# 2_mb_conn.net
KiCad netlist of a schematic drawn in Altium Designer
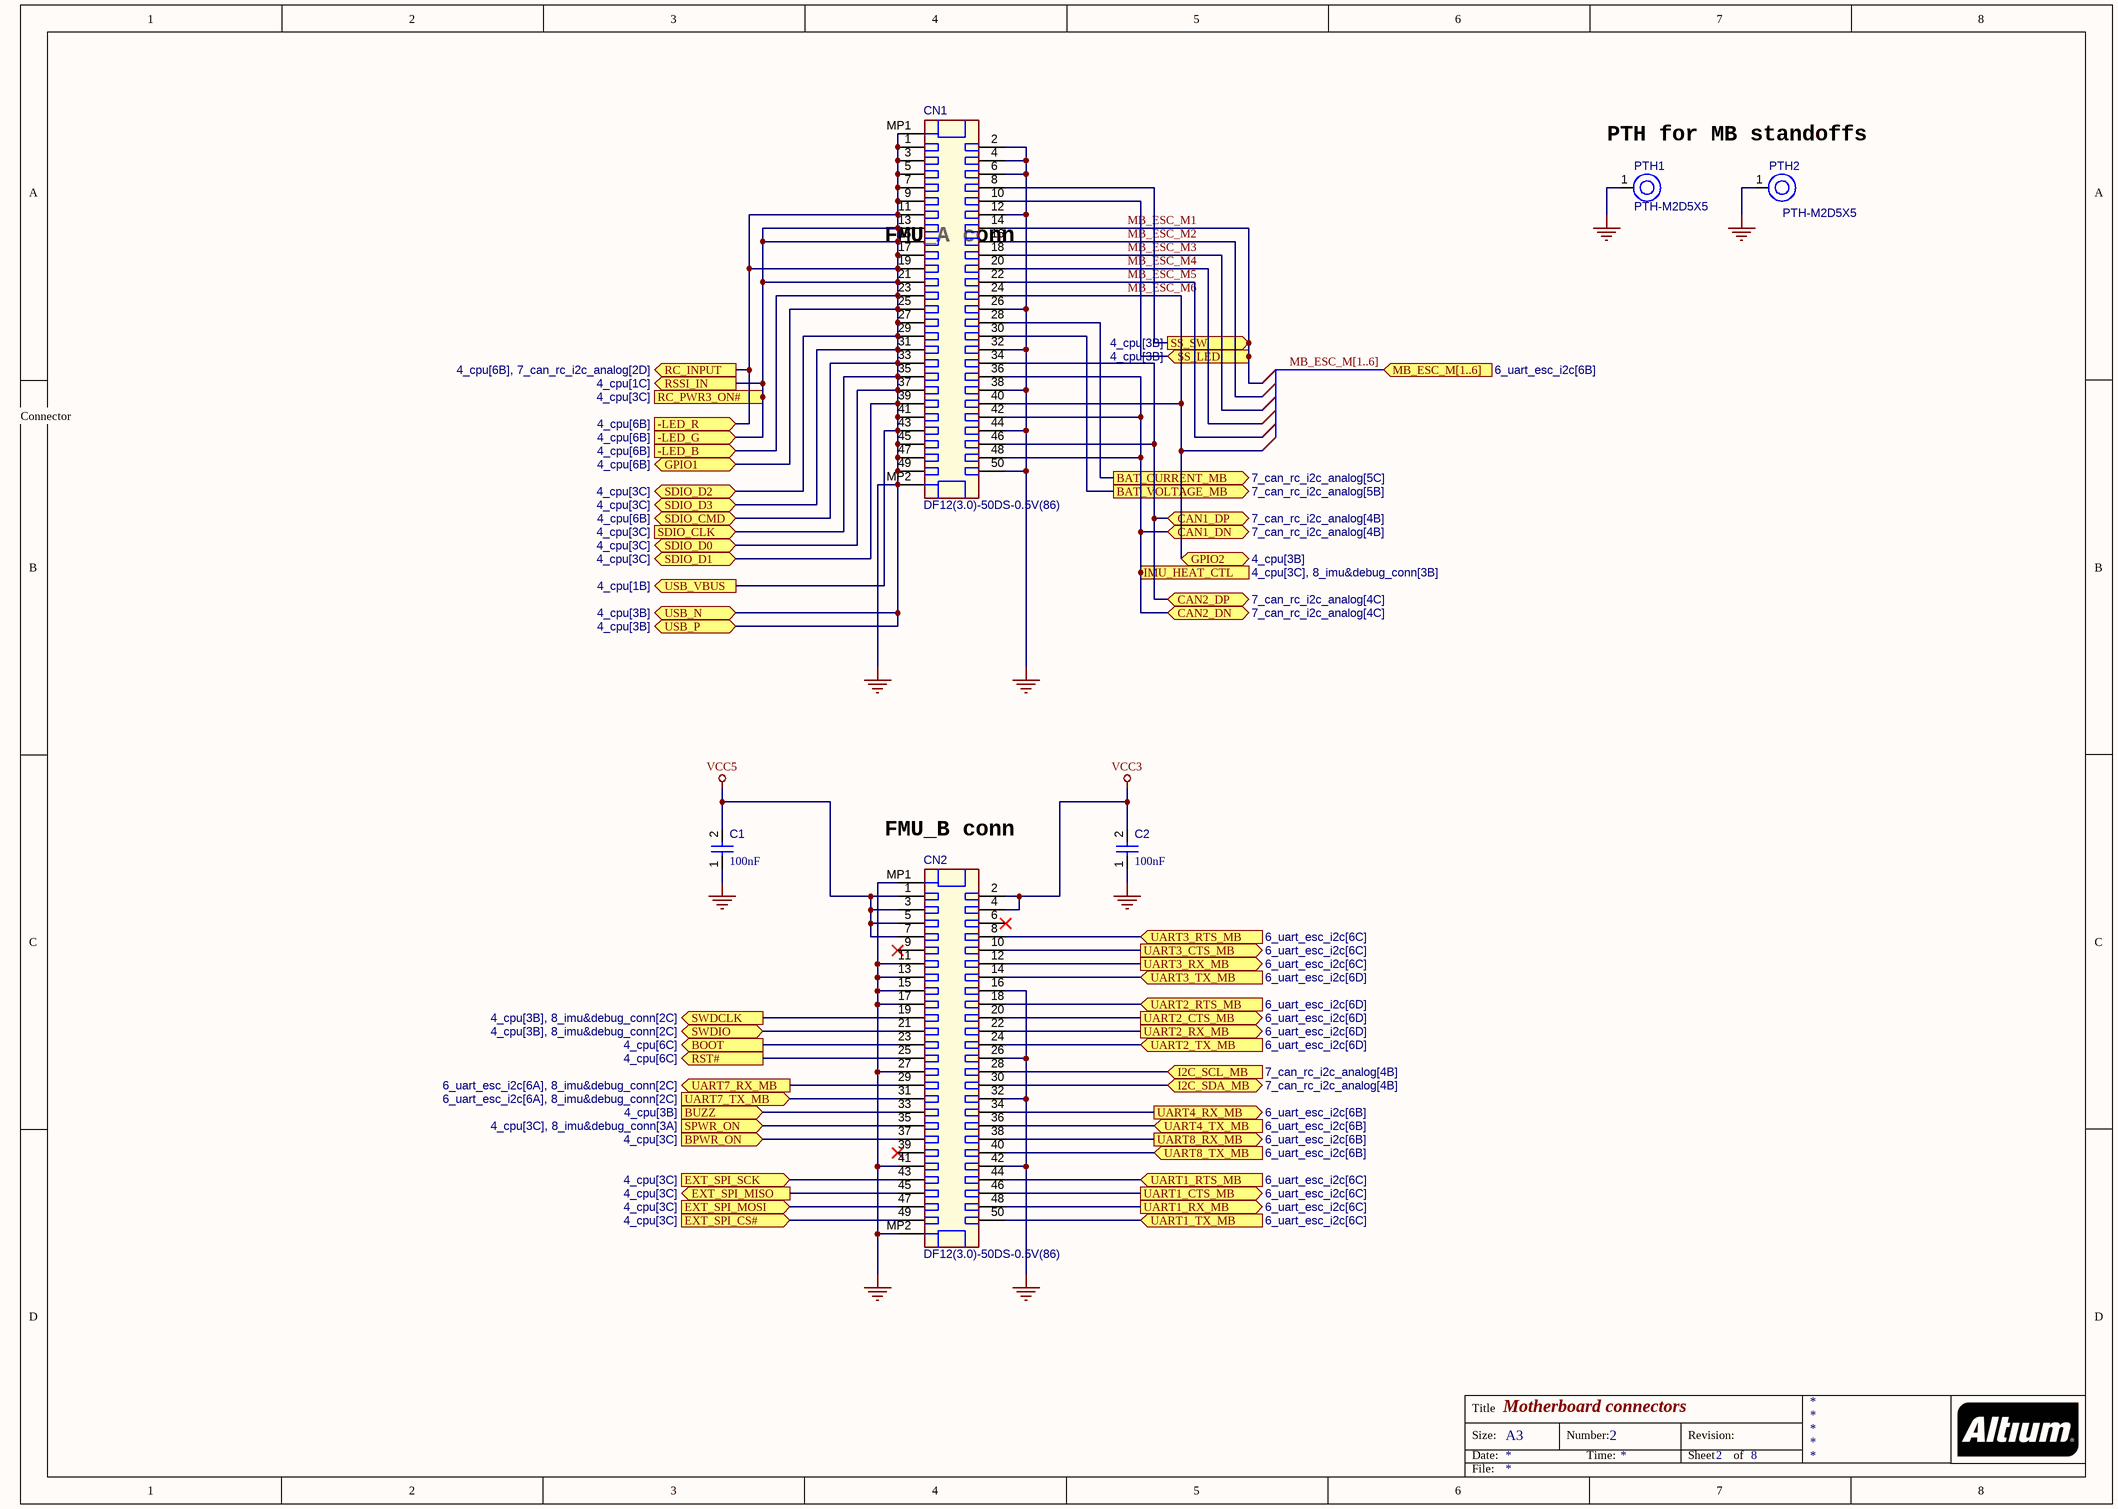
[diagram p0: 2_mb_conn.SchDoc]

(export (version "E")
  (design (tool "Eeschema 10.0.6"))
  (components
    (comp (ref "C1")
      (value "100nF")
      (footprint "CAPC0402(1005)60_L")
      (description "Chip Capacitor, 100nF +/-20%, 10V, 0402, Thickness 0.6 mm")
      (fields (field (name "TOLERANCE") "20%") (field (name "Comment") "Capacitor 100nF +/-20% 10V 0402"))
      (libsource (lib "SKA- Automa玢o de Engenharias") (part "CAP-NP-2"))
    )
    (comp (ref "C2")
      (value "100nF")
      (footprint "CAPC0402(1005)60_L")
      (description "Chip Capacitor, 100nF +/-20%, 10V, 0402, Thickness 0.6 mm")
      (fields (field (name "TOLERANCE") "20%") (field (name "Comment") "Capacitor 100nF +/-20% 10V 0402"))
      (libsource (lib "SKA- Automa玢o de Engenharias") (part "CAP-NP-2"))
    )
    (comp (ref "CN1")
      (value "DF12(3.0)-50DS-0.5V(86)")
      (footprint "HIRO-DF12(3.0)-50DS-0.5V_V")
      (description "Receptacle Connector, 50 V, 0.3 A, -45 to 125 degC, RoHS, Tape and Reel")
      (fields (field (name "PART NUMBER") "DF12"))
      (libsource (lib "SKA- Automa玢o de Engenharias") (part "CMP-00111-4"))
    )
    (comp (ref "CN2")
      (value "DF12(3.0)-50DS-0.5V(86)")
      (footprint "HIRO-DF12(3.0)-50DS-0.5V_V")
      (description "Receptacle Connector, 50 V, 0.3 A, -45 to 125 degC, RoHS, Tape and Reel")
      (fields (field (name "PART NUMBER") "DF12"))
      (libsource (lib "SKA- Automa玢o de Engenharias") (part "CMP-00111-4"))
    )
    (comp (ref "PTH1")
      (value "PTH-M2D5X5")
      (footprint "PTH-M2D5X5")
      (description "M2 PTH (2.5mm), 5mm pad")
      (libsource (lib "<Company> Server") (part "CMP-00028-00000-1"))
    )
    (comp (ref "PTH2")
      (value "PTH-M2D5X5")
      (footprint "PTH-M2D5X5")
      (description "M2 PTH (2.5mm), 5mm pad")
      (libsource (lib "<Company> Server") (part "CMP-00028-00000-1"))
    )
  )
  (nets
    (net (code "1") (name "/BAT_CURRENT_MB") (class "Default")
      (node (ref "CN1") (pin "28") (pinfunction "28_28") (pintype "passive"))
    )
    (net (code "2") (name "/BAT_VOLTAGE_MB") (class "Default")
      (node (ref "CN1") (pin "30") (pinfunction "30_30") (pintype "passive"))
    )
    (net (code "3") (name "/BOOT") (class "Default")
      (node (ref "CN2") (pin "23") (pinfunction "23_23") (pintype "passive"))
    )
    (net (code "4") (name "/BPWR_ON") (class "Default")
      (node (ref "CN2") (pin "37") (pinfunction "37_37") (pintype "passive"))
    )
    (net (code "5") (name "/BUZZ") (class "Default")
      (node (ref "CN2") (pin "33") (pinfunction "33_33") (pintype "passive"))
    )
    (net (code "6") (name "/CAN1_DN") (class "Default")
      (node (ref "CN1") (pin "36") (pinfunction "36_36") (pintype "passive"))
      (node (ref "CN1") (pin "42") (pinfunction "42_42") (pintype "passive"))
      (node (ref "CN1") (pin "48") (pinfunction "48_48") (pintype "passive"))
    )
    (net (code "7") (name "/CAN1_DP") (class "Default")
      (node (ref "CN1") (pin "34") (pinfunction "34_34") (pintype "passive"))
      (node (ref "CN1") (pin "46") (pinfunction "46_46") (pintype "passive"))
    )
    (net (code "8") (name "/EXT_SPI_CS#") (class "Default")
      (node (ref "CN2") (pin "49") (pinfunction "49_49") (pintype "passive"))
    )
    (net (code "9") (name "/EXT_SPI_MISO") (class "Default")
      (node (ref "CN2") (pin "45") (pinfunction "45_45") (pintype "passive"))
    )
    (net (code "10") (name "/EXT_SPI_MOSI") (class "Default")
      (node (ref "CN2") (pin "47") (pinfunction "47_47") (pintype "passive"))
    )
    (net (code "11") (name "/EXT_SPI_SCK") (class "Default")
      (node (ref "CN2") (pin "43") (pinfunction "43_43") (pintype "passive"))
    )
    (net (code "12") (name "/I2C_SCL_MB") (class "Default")
      (node (ref "CN2") (pin "28") (pinfunction "28_28") (pintype "passive"))
    )
    (net (code "13") (name "/I2C_SDA_MB") (class "Default")
      (node (ref "CN2") (pin "30") (pinfunction "30_30") (pintype "passive"))
    )
    (net (code "14") (name "/MB_ESC_M1") (class "Default")
      (node (ref "CN1") (pin "10") (pinfunction "10_10") (pintype "passive"))
      (node (ref "CN1") (pin "14") (pinfunction "14_14") (pintype "passive"))
      (node (ref "CN1") (pin "8") (pinfunction "8_8") (pintype "passive"))
    )
    (net (code "15") (name "/MB_ESC_M2") (class "Default")
      (node (ref "CN1") (pin "16") (pinfunction "16_16") (pintype "passive"))
    )
    (net (code "16") (name "/MB_ESC_M3") (class "Default")
      (node (ref "CN1") (pin "18") (pinfunction "18_18") (pintype "passive"))
    )
    (net (code "17") (name "/MB_ESC_M4") (class "Default")
      (node (ref "CN1") (pin "20") (pinfunction "20_20") (pintype "passive"))
    )
    (net (code "18") (name "/MB_ESC_M5") (class "Default")
      (node (ref "CN1") (pin "22") (pinfunction "22_22") (pintype "passive"))
    )
    (net (code "19") (name "/MB_ESC_M6") (class "Default")
      (node (ref "CN1") (pin "24") (pinfunction "24_24") (pintype "passive"))
      (node (ref "CN1") (pin "40") (pinfunction "40_40") (pintype "passive"))
    )
    (net (code "21") (name "/RST#") (class "Default")
      (node (ref "CN2") (pin "25") (pinfunction "25_25") (pintype "passive"))
    )
    (net (code "22") (name "/SPWR_ON") (class "Default")
      (node (ref "CN2") (pin "35") (pinfunction "35_35") (pintype "passive"))
    )
    (net (code "23") (name "/SWDCLK") (class "Default")
      (node (ref "CN2") (pin "19") (pinfunction "19_19") (pintype "passive"))
    )
    (net (code "24") (name "/SWDIO") (class "Default")
      (node (ref "CN2") (pin "21") (pinfunction "21_21") (pintype "passive"))
    )
    (net (code "25") (name "/UART1_CTS_MB") (class "Default")
      (node (ref "CN2") (pin "46") (pinfunction "46_46") (pintype "passive"))
    )
    (net (code "26") (name "/UART1_RTS_MB") (class "Default")
      (node (ref "CN2") (pin "44") (pinfunction "44_44") (pintype "passive"))
    )
    (net (code "27") (name "/UART1_RX_MB") (class "Default")
      (node (ref "CN2") (pin "48") (pinfunction "48_48") (pintype "passive"))
    )
    (net (code "28") (name "/UART1_TX_MB") (class "Default")
      (node (ref "CN2") (pin "50") (pinfunction "50_50") (pintype "passive"))
    )
    (net (code "29") (name "/UART2_CTS_MB") (class "Default")
      (node (ref "CN2") (pin "20") (pinfunction "20_20") (pintype "passive"))
    )
    (net (code "30") (name "/UART2_RTS_MB") (class "Default")
      (node (ref "CN2") (pin "18") (pinfunction "18_18") (pintype "passive"))
    )
    (net (code "31") (name "/UART2_RX_MB") (class "Default")
      (node (ref "CN2") (pin "22") (pinfunction "22_22") (pintype "passive"))
    )
    (net (code "32") (name "/UART2_TX_MB") (class "Default")
      (node (ref "CN2") (pin "24") (pinfunction "24_24") (pintype "passive"))
    )
    (net (code "33") (name "/UART3_CTS_MB") (class "Default")
      (node (ref "CN2") (pin "10") (pinfunction "10_10") (pintype "passive"))
    )
    (net (code "34") (name "/UART3_RTS_MB") (class "Default")
      (node (ref "CN2") (pin "8") (pinfunction "8_8") (pintype "passive"))
    )
    (net (code "35") (name "/UART3_RX_MB") (class "Default")
      (node (ref "CN2") (pin "12") (pinfunction "12_12") (pintype "passive"))
    )
    (net (code "36") (name "/UART3_TX_MB") (class "Default")
      (node (ref "CN2") (pin "14") (pinfunction "14_14") (pintype "passive"))
    )
    (net (code "37") (name "/UART4_RX_MB") (class "Default")
      (node (ref "CN2") (pin "34") (pinfunction "34_34") (pintype "passive"))
    )
    (net (code "38") (name "/UART4_TX_MB") (class "Default")
      (node (ref "CN2") (pin "36") (pinfunction "36_36") (pintype "passive"))
    )
    (net (code "39") (name "/UART7_RX_MB") (class "Default")
      (node (ref "CN2") (pin "29") (pinfunction "29_29") (pintype "passive"))
    )
    (net (code "40") (name "/UART7_TX_MB") (class "Default")
      (node (ref "CN2") (pin "31") (pinfunction "31_31") (pintype "passive"))
    )
    (net (code "41") (name "/UART8_RX_MB") (class "Default")
      (node (ref "CN2") (pin "38") (pinfunction "38_38") (pintype "passive"))
    )
    (net (code "42") (name "/UART8_TX_MB") (class "Default")
      (node (ref "CN2") (pin "40") (pinfunction "40_40") (pintype "passive"))
    )
    (net (code "43") (name "GND") (class "Default")
      (node (ref "C1") (pin "1") (pinfunction "1_1") (pintype "passive"))
      (node (ref "C2") (pin "1") (pinfunction "1_1") (pintype "passive"))
      (node (ref "CN1") (pin "1") (pinfunction "1_1") (pintype "passive"))
      (node (ref "CN1") (pin "11") (pinfunction "11_11") (pintype "passive"))
      (node (ref "CN1") (pin "12") (pinfunction "12_12") (pintype "passive"))
      (node (ref "CN1") (pin "13") (pinfunction "13_13") (pintype "passive"))
      (node (ref "CN1") (pin "15") (pinfunction "15_15") (pintype "passive"))
      (node (ref "CN1") (pin "17") (pinfunction "17_17") (pintype "passive"))
      (node (ref "CN1") (pin "19") (pinfunction "19_19") (pintype "passive"))
      (node (ref "CN1") (pin "2") (pinfunction "2_2") (pintype "passive"))
      (node (ref "CN1") (pin "21") (pinfunction "21_21") (pintype "passive"))
      (node (ref "CN1") (pin "23") (pinfunction "23_23") (pintype "passive"))
      (node (ref "CN1") (pin "25") (pinfunction "25_25") (pintype "passive"))
      (node (ref "CN1") (pin "26") (pinfunction "26_26") (pintype "passive"))
      (node (ref "CN1") (pin "27") (pinfunction "27_27") (pintype "passive"))
      (node (ref "CN1") (pin "29") (pinfunction "29_29") (pintype "passive"))
      (node (ref "CN1") (pin "3") (pinfunction "3_3") (pintype "passive"))
      (node (ref "CN1") (pin "31") (pinfunction "31_31") (pintype "passive"))
      (node (ref "CN1") (pin "32") (pinfunction "32_32") (pintype "passive"))
      (node (ref "CN1") (pin "33") (pinfunction "33_33") (pintype "passive"))
      (node (ref "CN1") (pin "35") (pinfunction "35_35") (pintype "passive"))
      (node (ref "CN1") (pin "37") (pinfunction "37_37") (pintype "passive"))
      (node (ref "CN1") (pin "38") (pinfunction "38_38") (pintype "passive"))
      (node (ref "CN1") (pin "39") (pinfunction "39_39") (pintype "passive"))
      (node (ref "CN1") (pin "4") (pinfunction "4_4") (pintype "passive"))
      (node (ref "CN1") (pin "41") (pinfunction "41_41") (pintype "passive"))
      (node (ref "CN1") (pin "43") (pinfunction "43_43") (pintype "passive"))
      (node (ref "CN1") (pin "44") (pinfunction "44_44") (pintype "passive"))
      (node (ref "CN1") (pin "45") (pinfunction "45_45") (pintype "passive"))
      (node (ref "CN1") (pin "47") (pinfunction "47_47") (pintype "passive"))
      (node (ref "CN1") (pin "49") (pinfunction "49_49") (pintype "passive"))
      (node (ref "CN1") (pin "5") (pinfunction "5_5") (pintype "passive"))
      (node (ref "CN1") (pin "50") (pinfunction "50_50") (pintype "passive"))
      (node (ref "CN1") (pin "6") (pinfunction "6_6") (pintype "passive"))
      (node (ref "CN1") (pin "7") (pinfunction "7_7") (pintype "passive"))
      (node (ref "CN1") (pin "9") (pinfunction "9_9") (pintype "passive"))
      (node (ref "CN1") (pin "MP1") (pinfunction "MP1_MP1") (pintype "passive"))
      (node (ref "CN1") (pin "MP2") (pinfunction "MP2_MP2") (pintype "passive"))
      (node (ref "CN2") (pin "11") (pinfunction "11_11") (pintype "passive"))
      (node (ref "CN2") (pin "13") (pinfunction "13_13") (pintype "passive"))
      (node (ref "CN2") (pin "15") (pinfunction "15_15") (pintype "passive"))
      (node (ref "CN2") (pin "16") (pinfunction "16_16") (pintype "passive"))
      (node (ref "CN2") (pin "17") (pinfunction "17_17") (pintype "passive"))
      (node (ref "CN2") (pin "26") (pinfunction "26_26") (pintype "passive"))
      (node (ref "CN2") (pin "27") (pinfunction "27_27") (pintype "passive"))
      (node (ref "CN2") (pin "32") (pinfunction "32_32") (pintype "passive"))
      (node (ref "CN2") (pin "41") (pinfunction "41_41") (pintype "passive"))
      (node (ref "CN2") (pin "42") (pinfunction "42_42") (pintype "passive"))
      (node (ref "CN2") (pin "MP1") (pinfunction "MP1_MP1") (pintype "passive"))
      (node (ref "CN2") (pin "MP2") (pinfunction "MP2_MP2") (pintype "passive"))
      (node (ref "PTH1") (pin "1") (pinfunction "H1_1") (pintype "passive"))
      (node (ref "PTH2") (pin "1") (pinfunction "H1_1") (pintype "passive"))
    )
    (net (code "44") (name "VCC3") (class "Default")
      (node (ref "C2") (pin "2") (pinfunction "2_2") (pintype "passive"))
      (node (ref "CN2") (pin "2") (pinfunction "2_2") (pintype "passive"))
      (node (ref "CN2") (pin "4") (pinfunction "4_4") (pintype "passive"))
    )
    (net (code "45") (name "VCC5") (class "Default")
      (node (ref "C1") (pin "2") (pinfunction "2_2") (pintype "passive"))
      (node (ref "CN2") (pin "1") (pinfunction "1_1") (pintype "passive"))
      (node (ref "CN2") (pin "3") (pinfunction "3_3") (pintype "passive"))
      (node (ref "CN2") (pin "5") (pinfunction "5_5") (pintype "passive"))
      (node (ref "CN2") (pin "7") (pinfunction "7_7") (pintype "passive"))
    )
    (net (code "46") (name "unconnected-(CN2-Pad6)") (class "Default")
      (node (ref "CN2") (pin "6") (pinfunction "6_6") (pintype "passive+no_connect"))
    )
    (net (code "47") (name "unconnected-(CN2-Pad9)") (class "Default")
      (node (ref "CN2") (pin "9") (pinfunction "9_9") (pintype "passive+no_connect"))
    )
    (net (code "48") (name "unconnected-(CN2-Pad39)") (class "Default")
      (node (ref "CN2") (pin "39") (pinfunction "39_39") (pintype "passive+no_connect"))
    )
  )
)
